# C-03_eMMC_NAND_TF_QSPI.net
KiCad netlist of a schematic drawn in Altium Designer
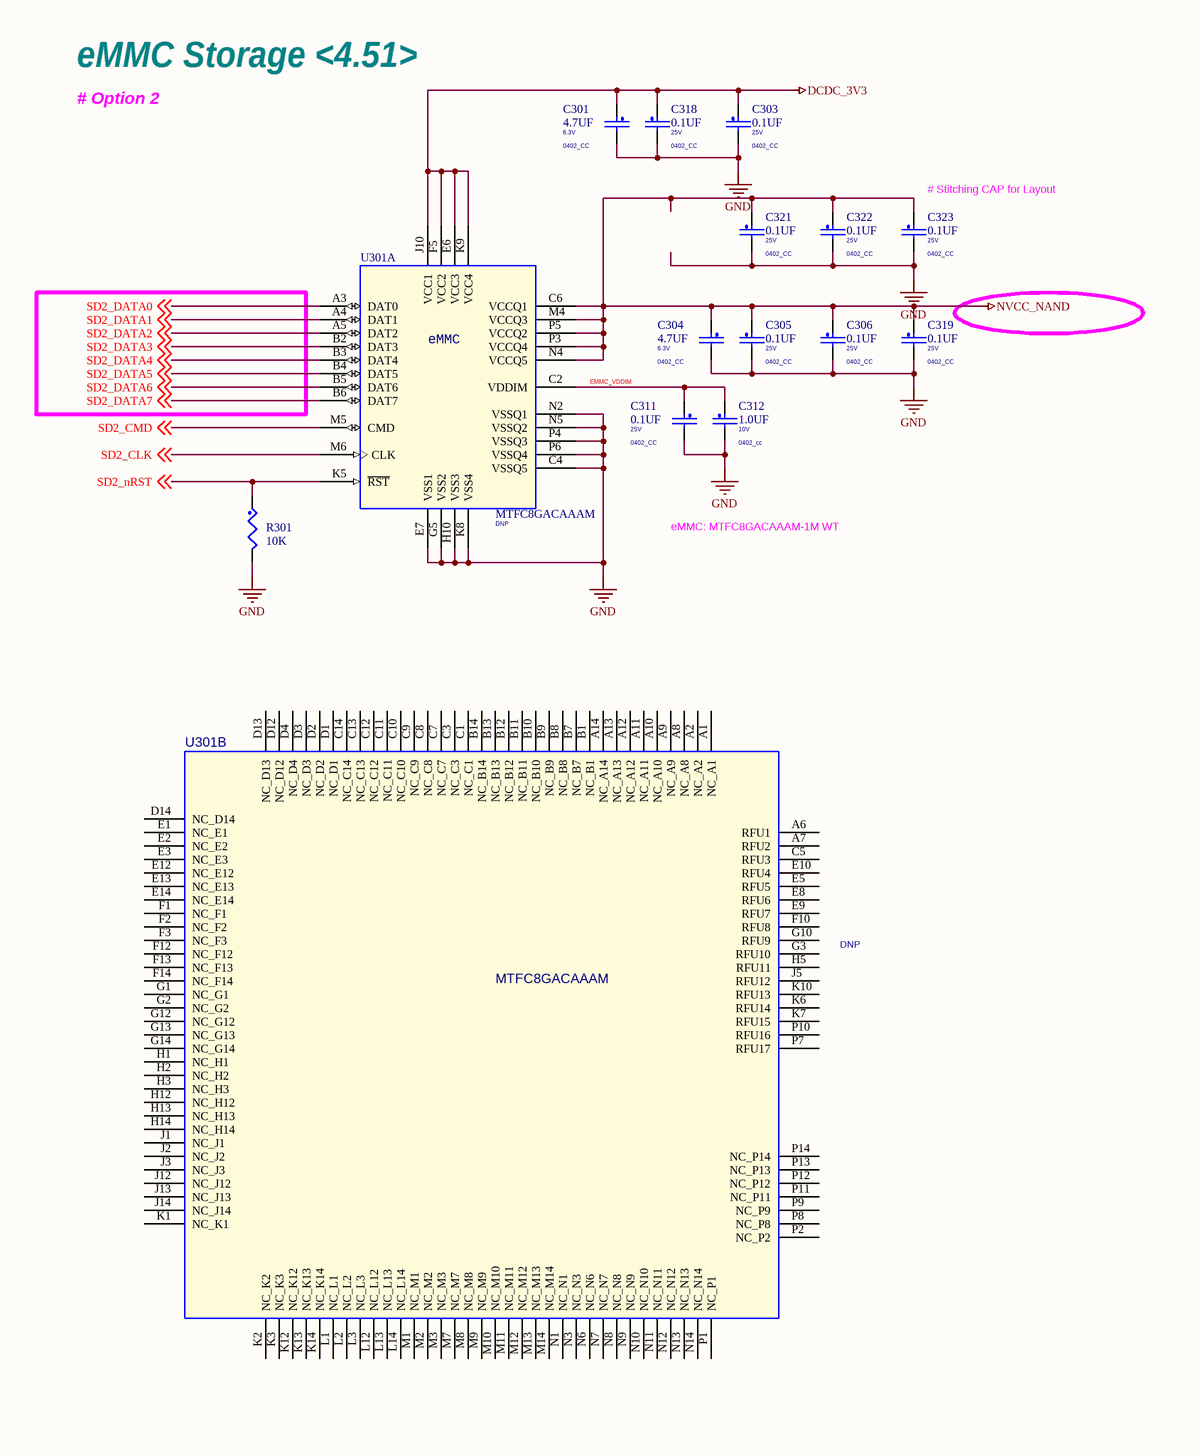
[diagram p0: C-03 eMMC_NAND_TF_QSPI.SchDoc, left]
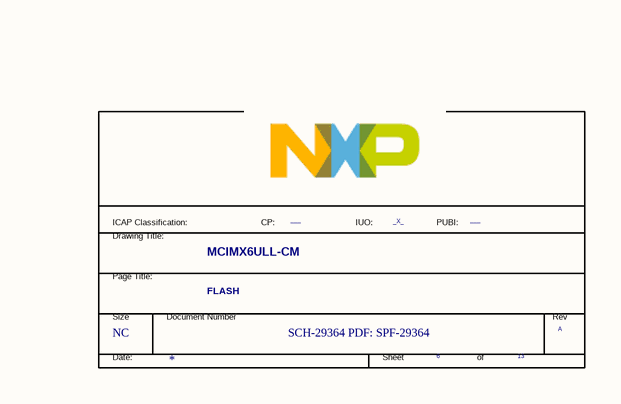
[diagram p1: C-03 eMMC_NAND_TF_QSPI.SchDoc, right]

(export (version "E")
  (design (tool "Eeschema 10.0.6"))
  (components
    (comp (ref "C301")
      (value "4.7UF")
      (footprint "C0402_H0.5mm")
      (description "CAP CER 4.7UF 6.3V 20% X5R 0402")
      (fields
        (field (name "PCB FOOTPRINT") "0402_CC")
        (field (name "VOLTAGE") "6.3V")
        (field (name "VOLTAGE RATING") "6.3V")
        (field (name "TOLERANCE") "20%")
      )
      (libsource (lib "*") (part "CAP_NP"))
    )
    (comp (ref "C303")
      (value "0.1UF")
      (footprint "C0402_H0.5mm")
      (description "CAP CER 0.1UF 25V 10% X5R 0402")
      (fields
        (field (name "TOLERANCE") "10%")
        (field (name "VOLTAGE") "25V")
        (field (name "PCB FOOTPRINT") "0402_CC")
      )
      (libsource (lib "*") (part "CAP_NP"))
    )
    (comp (ref "C304")
      (value "4.7UF")
      (footprint "C0402_H0.5mm")
      (description "CAP CER 4.7UF 6.3V 20% X5R 0402")
      (fields
        (field (name "TOLERANCE") "20%")
        (field (name "VOLTAGE RATING") "6.3V")
        (field (name "VOLTAGE") "6.3V")
        (field (name "PCB FOOTPRINT") "0402_CC")
      )
      (libsource (lib "*") (part "CAP_NP"))
    )
    (comp (ref "C305")
      (value "0.1UF")
      (footprint "C0402_H0.5mm")
      (description "CAP CER 0.1UF 25V 10% X5R 0402")
      (fields
        (field (name "VOLTAGE") "25V")
        (field (name "TOLERANCE") "10%")
        (field (name "PCB FOOTPRINT") "0402_CC")
      )
      (libsource (lib "*") (part "CAP_NP"))
    )
    (comp (ref "C306")
      (value "0.1UF")
      (footprint "C0402_H0.5mm")
      (description "CAP CER 0.1UF 25V 10% X5R 0402")
      (fields
        (field (name "VOLTAGE") "25V")
        (field (name "TOLERANCE") "10%")
        (field (name "PCB FOOTPRINT") "0402_CC")
      )
      (libsource (lib "*") (part "CAP_NP"))
    )
    (comp (ref "C311")
      (value "0.1UF")
      (footprint "C0402_H0.5mm")
      (description "CAP CER 0.1UF 25V 10% X5R 0402")
      (fields
        (field (name "VOLTAGE") "25V")
        (field (name "TOLERANCE") "10%")
        (field (name "PCB FOOTPRINT") "0402_CC")
      )
      (libsource (lib "*") (part "CAP_NP"))
    )
    (comp (ref "C312")
      (value "1.0UF")
      (footprint "C0402_H0.5mm")
      (description "CAP CER 1.0UF 10V 10% X5R 0402")
      (fields (field (name "VOLTAGE") "10V") (field (name "PCB FOOTPRINT") "0402_cc"))
      (libsource (lib "*") (part "CAP_NP"))
    )
    (comp (ref "C318")
      (value "0.1UF")
      (footprint "C0402_H0.5mm")
      (description "CAP CER 0.1UF 25V 10% X5R 0402")
      (fields
        (field (name "VOLTAGE") "25V")
        (field (name "TOLERANCE") "10%")
        (field (name "PCB FOOTPRINT") "0402_CC")
      )
      (libsource (lib "*") (part "CAP_NP"))
    )
    (comp (ref "C319")
      (value "0.1UF")
      (footprint "C0402_H0.5mm")
      (description "CAP CER 0.1UF 25V 10% X5R 0402")
      (fields
        (field (name "TOLERANCE") "10%")
        (field (name "VOLTAGE") "25V")
        (field (name "PCB FOOTPRINT") "0402_CC")
      )
      (libsource (lib "*") (part "CAP_NP"))
    )
    (comp (ref "C321")
      (value "0.1UF")
      (footprint "C0402_H0.5mm")
      (description "CAP CER 0.1UF 25V 10% X5R 0402")
      (fields
        (field (name "TOLERANCE") "10%")
        (field (name "VOLTAGE") "25V")
        (field (name "PCB FOOTPRINT") "0402_CC")
      )
      (libsource (lib "*") (part "CAP_NP"))
    )
    (comp (ref "C322")
      (value "0.1UF")
      (footprint "C0402_H0.5mm")
      (description "CAP CER 0.1UF 25V 10% X5R 0402")
      (fields
        (field (name "VOLTAGE") "25V")
        (field (name "TOLERANCE") "10%")
        (field (name "PCB FOOTPRINT") "0402_CC")
      )
      (libsource (lib "*") (part "CAP_NP"))
    )
    (comp (ref "C323")
      (value "0.1UF")
      (footprint "C0402_H0.5mm")
      (description "CAP CER 0.1UF 25V 10% X5R 0402")
      (fields
        (field (name "VOLTAGE") "25V")
        (field (name "TOLERANCE") "10%")
        (field (name "PCB FOOTPRINT") "0402_CC")
      )
      (libsource (lib "*") (part "CAP_NP"))
    )
    (comp (ref "R301")
      (value "10K")
      (footprint "R0402_H0.35mm")
      (description "RES MF 10K 1/16W 5% 0402")
      (fields (field (name "TOLERANCE") "5%"))
      (libsource (lib "*") (part "RES"))
    )
    (comp (ref "U301")
      (value "MTFC8GACAAAM")
      (footprint "BGA153_11.5x13mm")
      (description "IC MEM NAND FLASH 8GB MMC 4.51 CTLR 2.7-3.6V FBGA153")
      (fields (field (name "ASSY_OPT") "DNP"))
      (libsource (lib "") (part "MTFC4GMVEA_WFBGA_153P_1"))
    )
  )
  (nets
    (net (code "1") (name "/EMMC_VDDIM") (class "Default")
      (node (ref "C311") (pin "1") (pinfunction "1_1") (pintype "passive"))
      (node (ref "C312") (pin "1") (pinfunction "1_1") (pintype "passive"))
      (node (ref "U301") (pin "C2") (pinfunction "VDDIM_C2") (pintype "power_in"))
    )
    (net (code "2") (name "DCDC_3V3") (class "Default")
      (node (ref "C301") (pin "1") (pinfunction "1_1") (pintype "passive"))
      (node (ref "C303") (pin "1") (pinfunction "1_1") (pintype "passive"))
      (node (ref "C318") (pin "1") (pinfunction "1_1") (pintype "passive"))
      (node (ref "U301") (pin "E6") (pinfunction "VCC3_E6") (pintype "power_in"))
      (node (ref "U301") (pin "F5") (pinfunction "VCC2_F5") (pintype "power_in"))
      (node (ref "U301") (pin "J10") (pinfunction "VCC1_J10") (pintype "power_in"))
      (node (ref "U301") (pin "K9") (pinfunction "VCC4_K9") (pintype "power_in"))
    )
    (net (code "3") (name "GND") (class "Default")
      (node (ref "C301") (pin "2") (pinfunction "2_2") (pintype "passive"))
      (node (ref "C303") (pin "2") (pinfunction "2_2") (pintype "passive"))
      (node (ref "C304") (pin "2") (pinfunction "2_2") (pintype "passive"))
      (node (ref "C305") (pin "2") (pinfunction "2_2") (pintype "passive"))
      (node (ref "C306") (pin "2") (pinfunction "2_2") (pintype "passive"))
      (node (ref "C311") (pin "2") (pinfunction "2_2") (pintype "passive"))
      (node (ref "C312") (pin "2") (pinfunction "2_2") (pintype "passive"))
      (node (ref "C318") (pin "2") (pinfunction "2_2") (pintype "passive"))
      (node (ref "C319") (pin "2") (pinfunction "2_2") (pintype "passive"))
      (node (ref "C321") (pin "2") (pinfunction "2_2") (pintype "passive"))
      (node (ref "C322") (pin "2") (pinfunction "2_2") (pintype "passive"))
      (node (ref "C323") (pin "2") (pinfunction "2_2") (pintype "passive"))
      (node (ref "R301") (pin "2") (pinfunction "2_2") (pintype "passive"))
      (node (ref "U301") (pin "C4") (pinfunction "VSSQ5_C4") (pintype "power_in"))
      (node (ref "U301") (pin "E7") (pinfunction "VSS1_E7") (pintype "power_in"))
      (node (ref "U301") (pin "G5") (pinfunction "VSS2_G5") (pintype "power_in"))
      (node (ref "U301") (pin "H10") (pinfunction "VSS3_H10") (pintype "power_in"))
      (node (ref "U301") (pin "K8") (pinfunction "VSS4_K8") (pintype "power_in"))
      (node (ref "U301") (pin "N2") (pinfunction "VSSQ1_N2") (pintype "power_in"))
      (node (ref "U301") (pin "N5") (pinfunction "VSSQ2_N5") (pintype "power_in"))
      (node (ref "U301") (pin "P4") (pinfunction "VSSQ3_P4") (pintype "power_in"))
      (node (ref "U301") (pin "P6") (pinfunction "VSSQ4_P6") (pintype "power_in"))
    )
    (net (code "4") (name "NVCC_NAND") (class "Default")
      (node (ref "C304") (pin "1") (pinfunction "1_1") (pintype "passive"))
      (node (ref "C305") (pin "1") (pinfunction "1_1") (pintype "passive"))
      (node (ref "C306") (pin "1") (pinfunction "1_1") (pintype "passive"))
      (node (ref "C319") (pin "1") (pinfunction "1_1") (pintype "passive"))
      (node (ref "C321") (pin "1") (pinfunction "1_1") (pintype "passive"))
      (node (ref "C322") (pin "1") (pinfunction "1_1") (pintype "passive"))
      (node (ref "C323") (pin "1") (pinfunction "1_1") (pintype "passive"))
      (node (ref "U301") (pin "C6") (pinfunction "VCCQ1_C6") (pintype "power_in"))
      (node (ref "U301") (pin "M4") (pinfunction "VCCQ3_M4") (pintype "power_in"))
      (node (ref "U301") (pin "N4") (pinfunction "VCCQ5_N4") (pintype "power_in"))
      (node (ref "U301") (pin "P3") (pinfunction "VCCQ4_P3") (pintype "power_in"))
      (node (ref "U301") (pin "P5") (pinfunction "VCCQ2_P5") (pintype "power_in"))
    )
    (net (code "5") (name "SD2_CLK") (class "Default")
      (node (ref "U301") (pin "M6") (pinfunction "CLK_M6") (pintype "input"))
    )
    (net (code "6") (name "SD2_CMD") (class "Default")
      (node (ref "U301") (pin "M5") (pinfunction "CMD_M5") (pintype "bidirectional"))
    )
    (net (code "7") (name "SD2_DATA0") (class "Default")
      (node (ref "U301") (pin "A3") (pinfunction "DAT0_A3") (pintype "bidirectional"))
    )
    (net (code "8") (name "SD2_DATA1") (class "Default")
      (node (ref "U301") (pin "A4") (pinfunction "DAT1_A4") (pintype "bidirectional"))
    )
    (net (code "9") (name "SD2_DATA2") (class "Default")
      (node (ref "U301") (pin "A5") (pinfunction "DAT2_A5") (pintype "bidirectional"))
    )
    (net (code "10") (name "SD2_DATA3") (class "Default")
      (node (ref "U301") (pin "B2") (pinfunction "DAT3_B2") (pintype "bidirectional"))
    )
    (net (code "11") (name "SD2_DATA4") (class "Default")
      (node (ref "U301") (pin "B3") (pinfunction "DAT4_B3") (pintype "bidirectional"))
    )
    (net (code "12") (name "SD2_DATA5") (class "Default")
      (node (ref "U301") (pin "B4") (pinfunction "DAT5_B4") (pintype "bidirectional"))
    )
    (net (code "13") (name "SD2_DATA6") (class "Default")
      (node (ref "U301") (pin "B5") (pinfunction "DAT6_B5") (pintype "bidirectional"))
    )
    (net (code "14") (name "SD2_DATA7") (class "Default")
      (node (ref "U301") (pin "B6") (pinfunction "DAT7_B6") (pintype "bidirectional"))
    )
    (net (code "15") (name "SD2_nRST") (class "Default")
      (node (ref "R301") (pin "1") (pinfunction "1_1") (pintype "passive"))
      (node (ref "U301") (pin "K5") (pinfunction "~{RST}_K5") (pintype "input"))
    )
    (net (code "16") (name "unconnected-(U301B-NC_A1-PadA1)") (class "Default")
      (node (ref "U301") (pin "A1") (pinfunction "NC_A1_A1") (pintype "passive"))
    )
    (net (code "17") (name "unconnected-(U301B-NC_A2-PadA2)") (class "Default")
      (node (ref "U301") (pin "A2") (pinfunction "NC_A2_A2") (pintype "passive"))
    )
    (net (code "18") (name "unconnected-(U301B-NC_A8-PadA8)") (class "Default")
      (node (ref "U301") (pin "A8") (pinfunction "NC_A8_A8") (pintype "passive"))
    )
    (net (code "19") (name "unconnected-(U301B-NC_A9-PadA9)") (class "Default")
      (node (ref "U301") (pin "A9") (pinfunction "NC_A9_A9") (pintype "passive"))
    )
    (net (code "20") (name "unconnected-(U301B-NC_A10-PadA10)") (class "Default")
      (node (ref "U301") (pin "A10") (pinfunction "NC_A10_A10") (pintype "passive"))
    )
    (net (code "21") (name "unconnected-(U301B-NC_A11-PadA11)") (class "Default")
      (node (ref "U301") (pin "A11") (pinfunction "NC_A11_A11") (pintype "passive"))
    )
    (net (code "22") (name "unconnected-(U301B-NC_A12-PadA12)") (class "Default")
      (node (ref "U301") (pin "A12") (pinfunction "NC_A12_A12") (pintype "passive"))
    )
    (net (code "23") (name "unconnected-(U301B-NC_A13-PadA13)") (class "Default")
      (node (ref "U301") (pin "A13") (pinfunction "NC_A13_A13") (pintype "passive"))
    )
    (net (code "24") (name "unconnected-(U301B-NC_A14-PadA14)") (class "Default")
      (node (ref "U301") (pin "A14") (pinfunction "NC_A14_A14") (pintype "passive"))
    )
    (net (code "25") (name "unconnected-(U301B-NC_B1-PadB1)") (class "Default")
      (node (ref "U301") (pin "B1") (pinfunction "NC_B1_B1") (pintype "passive"))
    )
    (net (code "26") (name "unconnected-(U301B-NC_B7-PadB7)") (class "Default")
      (node (ref "U301") (pin "B7") (pinfunction "NC_B7_B7") (pintype "passive"))
    )
    (net (code "27") (name "unconnected-(U301B-NC_B8-PadB8)") (class "Default")
      (node (ref "U301") (pin "B8") (pinfunction "NC_B8_B8") (pintype "passive"))
    )
    (net (code "28") (name "unconnected-(U301B-NC_B9-PadB9)") (class "Default")
      (node (ref "U301") (pin "B9") (pinfunction "NC_B9_B9") (pintype "passive"))
    )
    (net (code "29") (name "unconnected-(U301B-NC_B10-PadB10)") (class "Default")
      (node (ref "U301") (pin "B10") (pinfunction "NC_B10_B10") (pintype "passive"))
    )
    (net (code "30") (name "unconnected-(U301B-NC_B11-PadB11)") (class "Default")
      (node (ref "U301") (pin "B11") (pinfunction "NC_B11_B11") (pintype "passive"))
    )
    (net (code "31") (name "unconnected-(U301B-NC_B12-PadB12)") (class "Default")
      (node (ref "U301") (pin "B12") (pinfunction "NC_B12_B12") (pintype "passive"))
    )
    (net (code "32") (name "unconnected-(U301B-NC_B13-PadB13)") (class "Default")
      (node (ref "U301") (pin "B13") (pinfunction "NC_B13_B13") (pintype "passive"))
    )
    (net (code "33") (name "unconnected-(U301B-NC_B14-PadB14)") (class "Default")
      (node (ref "U301") (pin "B14") (pinfunction "NC_B14_B14") (pintype "passive"))
    )
    (net (code "34") (name "unconnected-(U301B-NC_C1-PadC1)") (class "Default")
      (node (ref "U301") (pin "C1") (pinfunction "NC_C1_C1") (pintype "passive"))
    )
    (net (code "35") (name "unconnected-(U301B-NC_C3-PadC3)") (class "Default")
      (node (ref "U301") (pin "C3") (pinfunction "NC_C3_C3") (pintype "passive"))
    )
    (net (code "36") (name "unconnected-(U301B-NC_C7-PadC7)") (class "Default")
      (node (ref "U301") (pin "C7") (pinfunction "NC_C7_C7") (pintype "passive"))
    )
    (net (code "37") (name "unconnected-(U301B-NC_C8-PadC8)") (class "Default")
      (node (ref "U301") (pin "C8") (pinfunction "NC_C8_C8") (pintype "passive"))
    )
    (net (code "38") (name "unconnected-(U301B-NC_C9-PadC9)") (class "Default")
      (node (ref "U301") (pin "C9") (pinfunction "NC_C9_C9") (pintype "passive"))
    )
    (net (code "39") (name "unconnected-(U301B-NC_C10-PadC10)") (class "Default")
      (node (ref "U301") (pin "C10") (pinfunction "NC_C10_C10") (pintype "passive"))
    )
    (net (code "40") (name "unconnected-(U301B-NC_C11-PadC11)") (class "Default")
      (node (ref "U301") (pin "C11") (pinfunction "NC_C11_C11") (pintype "passive"))
    )
    (net (code "41") (name "unconnected-(U301B-NC_C12-PadC12)") (class "Default")
      (node (ref "U301") (pin "C12") (pinfunction "NC_C12_C12") (pintype "passive"))
    )
    (net (code "42") (name "unconnected-(U301B-NC_C13-PadC13)") (class "Default")
      (node (ref "U301") (pin "C13") (pinfunction "NC_C13_C13") (pintype "passive"))
    )
    (net (code "43") (name "unconnected-(U301B-NC_C14-PadC14)") (class "Default")
      (node (ref "U301") (pin "C14") (pinfunction "NC_C14_C14") (pintype "passive"))
    )
    (net (code "44") (name "unconnected-(U301B-NC_D1-PadD1)") (class "Default")
      (node (ref "U301") (pin "D1") (pinfunction "NC_D1_D1") (pintype "passive"))
    )
    (net (code "45") (name "unconnected-(U301B-NC_D2-PadD2)") (class "Default")
      (node (ref "U301") (pin "D2") (pinfunction "NC_D2_D2") (pintype "passive"))
    )
    (net (code "46") (name "unconnected-(U301B-NC_D3-PadD3)") (class "Default")
      (node (ref "U301") (pin "D3") (pinfunction "NC_D3_D3") (pintype "passive"))
    )
    (net (code "47") (name "unconnected-(U301B-NC_D4-PadD4)") (class "Default")
      (node (ref "U301") (pin "D4") (pinfunction "NC_D4_D4") (pintype "passive"))
    )
    (net (code "48") (name "unconnected-(U301B-NC_D12-PadD12)") (class "Default")
      (node (ref "U301") (pin "D12") (pinfunction "NC_D12_D12") (pintype "passive"))
    )
    (net (code "49") (name "unconnected-(U301B-NC_D13-PadD13)") (class "Default")
      (node (ref "U301") (pin "D13") (pinfunction "NC_D13_D13") (pintype "passive"))
    )
    (net (code "50") (name "unconnected-(U301B-NC_D14-PadD14)") (class "Default")
      (node (ref "U301") (pin "D14") (pinfunction "NC_D14_D14") (pintype "passive"))
    )
    (net (code "51") (name "unconnected-(U301B-NC_E1-PadE1)") (class "Default")
      (node (ref "U301") (pin "E1") (pinfunction "NC_E1_E1") (pintype "passive"))
    )
    (net (code "52") (name "unconnected-(U301B-NC_E2-PadE2)") (class "Default")
      (node (ref "U301") (pin "E2") (pinfunction "NC_E2_E2") (pintype "passive"))
    )
    (net (code "53") (name "unconnected-(U301B-NC_E3-PadE3)") (class "Default")
      (node (ref "U301") (pin "E3") (pinfunction "NC_E3_E3") (pintype "passive"))
    )
    (net (code "54") (name "unconnected-(U301B-NC_E12-PadE12)") (class "Default")
      (node (ref "U301") (pin "E12") (pinfunction "NC_E12_E12") (pintype "passive"))
    )
    (net (code "55") (name "unconnected-(U301B-NC_E13-PadE13)") (class "Default")
      (node (ref "U301") (pin "E13") (pinfunction "NC_E13_E13") (pintype "passive"))
    )
    (net (code "56") (name "unconnected-(U301B-NC_E14-PadE14)") (class "Default")
      (node (ref "U301") (pin "E14") (pinfunction "NC_E14_E14") (pintype "passive"))
    )
    (net (code "57") (name "unconnected-(U301B-NC_F1-PadF1)") (class "Default")
      (node (ref "U301") (pin "F1") (pinfunction "NC_F1_F1") (pintype "passive"))
    )
    (net (code "58") (name "unconnected-(U301B-NC_F2-PadF2)") (class "Default")
      (node (ref "U301") (pin "F2") (pinfunction "NC_F2_F2") (pintype "passive"))
    )
    (net (code "59") (name "unconnected-(U301B-NC_F3-PadF3)") (class "Default")
      (node (ref "U301") (pin "F3") (pinfunction "NC_F3_F3") (pintype "passive"))
    )
    (net (code "60") (name "unconnected-(U301B-NC_F12-PadF12)") (class "Default")
      (node (ref "U301") (pin "F12") (pinfunction "NC_F12_F12") (pintype "passive"))
    )
    (net (code "61") (name "unconnected-(U301B-NC_F13-PadF13)") (class "Default")
      (node (ref "U301") (pin "F13") (pinfunction "NC_F13_F13") (pintype "passive"))
    )
    (net (code "62") (name "unconnected-(U301B-NC_F14-PadF14)") (class "Default")
      (node (ref "U301") (pin "F14") (pinfunction "NC_F14_F14") (pintype "passive"))
    )
    (net (code "63") (name "unconnected-(U301B-NC_G1-PadG1)") (class "Default")
      (node (ref "U301") (pin "G1") (pinfunction "NC_G1_G1") (pintype "passive"))
    )
    (net (code "64") (name "unconnected-(U301B-NC_G2-PadG2)") (class "Default")
      (node (ref "U301") (pin "G2") (pinfunction "NC_G2_G2") (pintype "passive"))
    )
    (net (code "65") (name "unconnected-(U301B-NC_G12-PadG12)") (class "Default")
      (node (ref "U301") (pin "G12") (pinfunction "NC_G12_G12") (pintype "passive"))
    )
    (net (code "66") (name "unconnected-(U301B-NC_G13-PadG13)") (class "Default")
      (node (ref "U301") (pin "G13") (pinfunction "NC_G13_G13") (pintype "passive"))
    )
    (net (code "67") (name "unconnected-(U301B-NC_G14-PadG14)") (class "Default")
      (node (ref "U301") (pin "G14") (pinfunction "NC_G14_G14") (pintype "passive"))
    )
    (net (code "68") (name "unconnected-(U301B-NC_H1-PadH1)") (class "Default")
      (node (ref "U301") (pin "H1") (pinfunction "NC_H1_H1") (pintype "passive"))
    )
    (net (code "69") (name "unconnected-(U301B-NC_H2-PadH2)") (class "Default")
      (node (ref "U301") (pin "H2") (pinfunction "NC_H2_H2") (pintype "passive"))
    )
    (net (code "70") (name "unconnected-(U301B-NC_H3-PadH3)") (class "Default")
      (node (ref "U301") (pin "H3") (pinfunction "NC_H3_H3") (pintype "passive"))
    )
    (net (code "71") (name "unconnected-(U301B-NC_H12-PadH12)") (class "Default")
      (node (ref "U301") (pin "H12") (pinfunction "NC_H12_H12") (pintype "passive"))
    )
    (net (code "72") (name "unconnected-(U301B-NC_H13-PadH13)") (class "Default")
      (node (ref "U301") (pin "H13") (pinfunction "NC_H13_H13") (pintype "passive"))
    )
    (net (code "73") (name "unconnected-(U301B-NC_H14-PadH14)") (class "Default")
      (node (ref "U301") (pin "H14") (pinfunction "NC_H14_H14") (pintype "passive"))
    )
    (net (code "74") (name "unconnected-(U301B-NC_J1-PadJ1)") (class "Default")
      (node (ref "U301") (pin "J1") (pinfunction "NC_J1_J1") (pintype "passive"))
    )
    (net (code "75") (name "unconnected-(U301B-NC_J2-PadJ2)") (class "Default")
      (node (ref "U301") (pin "J2") (pinfunction "NC_J2_J2") (pintype "passive"))
    )
    (net (code "76") (name "unconnected-(U301B-NC_J3-PadJ3)") (class "Default")
      (node (ref "U301") (pin "J3") (pinfunction "NC_J3_J3") (pintype "passive"))
    )
    (net (code "77") (name "unconnected-(U301B-NC_J12-PadJ12)") (class "Default")
      (node (ref "U301") (pin "J12") (pinfunction "NC_J12_J12") (pintype "passive"))
    )
    (net (code "78") (name "unconnected-(U301B-NC_J13-PadJ13)") (class "Default")
      (node (ref "U301") (pin "J13") (pinfunction "NC_J13_J13") (pintype "passive"))
    )
    (net (code "79") (name "unconnected-(U301B-NC_J14-PadJ14)") (class "Default")
      (node (ref "U301") (pin "J14") (pinfunction "NC_J14_J14") (pintype "passive"))
    )
    (net (code "80") (name "unconnected-(U301B-NC_K1-PadK1)") (class "Default")
      (node (ref "U301") (pin "K1") (pinfunction "NC_K1_K1") (pintype "passive"))
    )
    (net (code "81") (name "unconnected-(U301B-NC_K2-PadK2)") (class "Default")
      (node (ref "U301") (pin "K2") (pinfunction "NC_K2_K2") (pintype "passive"))
    )
    (net (code "82") (name "unconnected-(U301B-NC_K3-PadK3)") (class "Default")
      (node (ref "U301") (pin "K3") (pinfunction "NC_K3_K3") (pintype "passive"))
    )
    (net (code "83") (name "unconnected-(U301B-NC_K12-PadK12)") (class "Default")
      (node (ref "U301") (pin "K12") (pinfunction "NC_K12_K12") (pintype "passive"))
    )
    (net (code "84") (name "unconnected-(U301B-NC_K13-PadK13)") (class "Default")
      (node (ref "U301") (pin "K13") (pinfunction "NC_K13_K13") (pintype "passive"))
    )
    (net (code "85") (name "unconnected-(U301B-NC_K14-PadK14)") (class "Default")
      (node (ref "U301") (pin "K14") (pinfunction "NC_K14_K14") (pintype "passive"))
    )
    (net (code "86") (name "unconnected-(U301B-NC_L1-PadL1)") (class "Default")
      (node (ref "U301") (pin "L1") (pinfunction "NC_L1_L1") (pintype "passive"))
    )
    (net (code "87") (name "unconnected-(U301B-NC_L2-PadL2)") (class "Default")
      (node (ref "U301") (pin "L2") (pinfunction "NC_L2_L2") (pintype "passive"))
    )
    (net (code "88") (name "unconnected-(U301B-NC_L3-PadL3)") (class "Default")
      (node (ref "U301") (pin "L3") (pinfunction "NC_L3_L3") (pintype "passive"))
    )
    (net (code "89") (name "unconnected-(U301B-NC_L12-PadL12)") (class "Default")
      (node (ref "U301") (pin "L12") (pinfunction "NC_L12_L12") (pintype "passive"))
    )
    (net (code "90") (name "unconnected-(U301B-NC_L13-PadL13)") (class "Default")
      (node (ref "U301") (pin "L13") (pinfunction "NC_L13_L13") (pintype "passive"))
    )
    (net (code "91") (name "unconnected-(U301B-NC_L14-PadL14)") (class "Default")
      (node (ref "U301") (pin "L14") (pinfunction "NC_L14_L14") (pintype "passive"))
    )
    (net (code "92") (name "unconnected-(U301B-NC_M1-PadM1)") (class "Default")
      (node (ref "U301") (pin "M1") (pinfunction "NC_M1_M1") (pintype "passive"))
    )
    (net (code "93") (name "unconnected-(U301B-NC_M2-PadM2)") (class "Default")
      (node (ref "U301") (pin "M2") (pinfunction "NC_M2_M2") (pintype "passive"))
    )
    (net (code "94") (name "unconnected-(U301B-NC_M3-PadM3)") (class "Default")
      (node (ref "U301") (pin "M3") (pinfunction "NC_M3_M3") (pintype "passive"))
    )
    (net (code "95") (name "unconnected-(U301B-NC_M7-PadM7)") (class "Default")
      (node (ref "U301") (pin "M7") (pinfunction "NC_M7_M7") (pintype "passive"))
    )
    (net (code "96") (name "unconnected-(U301B-NC_M8-PadM8)") (class "Default")
      (node (ref "U301") (pin "M8") (pinfunction "NC_M8_M8") (pintype "passive"))
    )
    (net (code "97") (name "unconnected-(U301B-NC_M9-PadM9)") (class "Default")
      (node (ref "U301") (pin "M9") (pinfunction "NC_M9_M9") (pintype "passive"))
    )
    (net (code "98") (name "unconnected-(U301B-NC_M10-PadM10)") (class "Default")
      (node (ref "U301") (pin "M10") (pinfunction "NC_M10_M10") (pintype "passive"))
    )
    (net (code "99") (name "unconnected-(U301B-NC_M11-PadM11)") (class "Default")
      (node (ref "U301") (pin "M11") (pinfunction "NC_M11_M11") (pintype "passive"))
    )
    (net (code "100") (name "unconnected-(U301B-NC_M12-PadM12)") (class "Default")
      (node (ref "U301") (pin "M12") (pinfunction "NC_M12_M12") (pintype "passive"))
    )
    (net (code "101") (name "unconnected-(U301B-NC_M13-PadM13)") (class "Default")
      (node (ref "U301") (pin "M13") (pinfunction "NC_M13_M13") (pintype "passive"))
    )
    (net (code "102") (name "unconnected-(U301B-NC_M14-PadM14)") (class "Default")
      (node (ref "U301") (pin "M14") (pinfunction "NC_M14_M14") (pintype "passive"))
    )
    (net (code "103") (name "unconnected-(U301B-NC_N1-PadN1)") (class "Default")
      (node (ref "U301") (pin "N1") (pinfunction "NC_N1_N1") (pintype "passive"))
    )
    (net (code "104") (name "unconnected-(U301B-NC_N3-PadN3)") (class "Default")
      (node (ref "U301") (pin "N3") (pinfunction "NC_N3_N3") (pintype "passive"))
    )
    (net (code "105") (name "unconnected-(U301B-NC_N6-PadN6)") (class "Default")
      (node (ref "U301") (pin "N6") (pinfunction "NC_N6_N6") (pintype "passive"))
    )
    (net (code "106") (name "unconnected-(U301B-NC_N7-PadN7)") (class "Default")
      (node (ref "U301") (pin "N7") (pinfunction "NC_N7_N7") (pintype "passive"))
    )
    (net (code "107") (name "unconnected-(U301B-NC_N8-PadN8)") (class "Default")
      (node (ref "U301") (pin "N8") (pinfunction "NC_N8_N8") (pintype "passive"))
    )
    (net (code "108") (name "unconnected-(U301B-NC_N9-PadN9)") (class "Default")
      (node (ref "U301") (pin "N9") (pinfunction "NC_N9_N9") (pintype "passive"))
    )
    (net (code "109") (name "unconnected-(U301B-NC_N10-PadN10)") (class "Default")
      (node (ref "U301") (pin "N10") (pinfunction "NC_N10_N10") (pintype "passive"))
    )
    (net (code "110") (name "unconnected-(U301B-NC_N11-PadN11)") (class "Default")
      (node (ref "U301") (pin "N11") (pinfunction "NC_N11_N11") (pintype "passive"))
    )
    (net (code "111") (name "unconnected-(U301B-NC_N12-PadN12)") (class "Default")
      (node (ref "U301") (pin "N12") (pinfunction "NC_N12_N12") (pintype "passive"))
    )
    (net (code "112") (name "unconnected-(U301B-NC_N13-PadN13)") (class "Default")
      (node (ref "U301") (pin "N13") (pinfunction "NC_N13_N13") (pintype "passive"))
    )
    (net (code "113") (name "unconnected-(U301B-NC_N14-PadN14)") (class "Default")
      (node (ref "U301") (pin "N14") (pinfunction "NC_N14_N14") (pintype "passive"))
    )
    (net (code "114") (name "unconnected-(U301B-NC_P1-PadP1)") (class "Default")
      (node (ref "U301") (pin "P1") (pinfunction "NC_P1_P1") (pintype "passive"))
    )
    (net (code "115") (name "unconnected-(U301B-NC_P2-PadP2)") (class "Default")
      (node (ref "U301") (pin "P2") (pinfunction "NC_P2_P2") (pintype "passive"))
    )
    (net (code "116") (name "unconnected-(U301B-NC_P8-PadP8)") (class "Default")
      (node (ref "U301") (pin "P8") (pinfunction "NC_P8_P8") (pintype "passive"))
    )
    (net (code "117") (name "unconnected-(U301B-NC_P9-PadP9)") (class "Default")
      (node (ref "U301") (pin "P9") (pinfunction "NC_P9_P9") (pintype "passive"))
    )
    (net (code "118") (name "unconnected-(U301B-NC_P11-PadP11)") (class "Default")
      (node (ref "U301") (pin "P11") (pinfunction "NC_P11_P11") (pintype "passive"))
    )
    (net (code "119") (name "unconnected-(U301B-NC_P12-PadP12)") (class "Default")
      (node (ref "U301") (pin "P12") (pinfunction "NC_P12_P12") (pintype "passive"))
    )
    (net (code "120") (name "unconnected-(U301B-NC_P13-PadP13)") (class "Default")
      (node (ref "U301") (pin "P13") (pinfunction "NC_P13_P13") (pintype "passive"))
    )
    (net (code "121") (name "unconnected-(U301B-NC_P14-PadP14)") (class "Default")
      (node (ref "U301") (pin "P14") (pinfunction "NC_P14_P14") (pintype "passive"))
    )
    (net (code "122") (name "unconnected-(U301B-RFU1-PadA6)") (class "Default")
      (node (ref "U301") (pin "A6") (pinfunction "RFU1_A6") (pintype "passive"))
    )
    (net (code "123") (name "unconnected-(U301B-RFU2-PadA7)") (class "Default")
      (node (ref "U301") (pin "A7") (pinfunction "RFU2_A7") (pintype "passive"))
    )
    (net (code "124") (name "unconnected-(U301B-RFU3-PadC5)") (class "Default")
      (node (ref "U301") (pin "C5") (pinfunction "RFU3_C5") (pintype "passive"))
    )
    (net (code "125") (name "unconnected-(U301B-RFU4-PadE10)") (class "Default")
      (node (ref "U301") (pin "E10") (pinfunction "RFU4_E10") (pintype "passive"))
    )
    (net (code "126") (name "unconnected-(U301B-RFU5-PadE5)") (class "Default")
      (node (ref "U301") (pin "E5") (pinfunction "RFU5_E5") (pintype "passive"))
    )
    (net (code "127") (name "unconnected-(U301B-RFU6-PadE8)") (class "Default")
      (node (ref "U301") (pin "E8") (pinfunction "RFU6_E8") (pintype "passive"))
    )
    (net (code "128") (name "unconnected-(U301B-RFU7-PadE9)") (class "Default")
      (node (ref "U301") (pin "E9") (pinfunction "RFU7_E9") (pintype "passive"))
    )
    (net (code "129") (name "unconnected-(U301B-RFU8-PadF10)") (class "Default")
      (node (ref "U301") (pin "F10") (pinfunction "RFU8_F10") (pintype "passive"))
    )
    (net (code "130") (name "unconnected-(U301B-RFU9-PadG10)") (class "Default")
      (node (ref "U301") (pin "G10") (pinfunction "RFU9_G10") (pintype "passive"))
    )
    (net (code "131") (name "unconnected-(U301B-RFU10-PadG3)") (class "Default")
      (node (ref "U301") (pin "G3") (pinfunction "RFU10_G3") (pintype "passive"))
    )
    (net (code "132") (name "unconnected-(U301B-RFU11-PadH5)") (class "Default")
      (node (ref "U301") (pin "H5") (pinfunction "RFU11_H5") (pintype "passive"))
    )
    (net (code "133") (name "unconnected-(U301B-RFU12-PadJ5)") (class "Default")
      (node (ref "U301") (pin "J5") (pinfunction "RFU12_J5") (pintype "passive"))
    )
    (net (code "134") (name "unconnected-(U301B-RFU13-PadK10)") (class "Default")
      (node (ref "U301") (pin "K10") (pinfunction "RFU13_K10") (pintype "passive"))
    )
    (net (code "135") (name "unconnected-(U301B-RFU14-PadK6)") (class "Default")
      (node (ref "U301") (pin "K6") (pinfunction "RFU14_K6") (pintype "passive"))
    )
    (net (code "136") (name "unconnected-(U301B-RFU15-PadK7)") (class "Default")
      (node (ref "U301") (pin "K7") (pinfunction "RFU15_K7") (pintype "passive"))
    )
    (net (code "137") (name "unconnected-(U301B-RFU16-PadP10)") (class "Default")
      (node (ref "U301") (pin "P10") (pinfunction "RFU16_P10") (pintype "passive"))
    )
    (net (code "138") (name "unconnected-(U301B-RFU17-PadP7)") (class "Default")
      (node (ref "U301") (pin "P7") (pinfunction "RFU17_P7") (pintype "passive"))
    )
  )
)
